# usb_uart.net
KiCad netlist of a schematic drawn in EAGLE
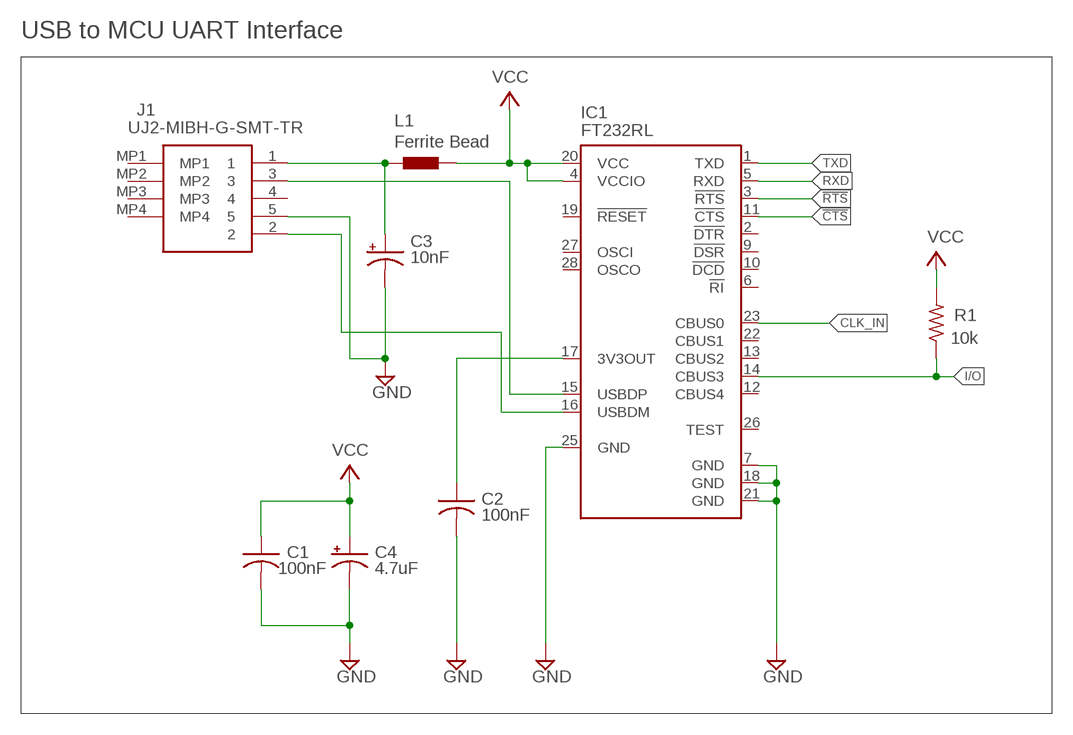
[diagram p0: schematic, sheet 1]

(export (version "E")
  (design (tool "Eeschema 10.0.6"))
  (components
    (comp (ref "C1")
      (value "100nF")
      (footprint "eagle-import:C0402")
      (libsource (lib "eagle-import") (part "C-USC0402"))
    )
    (comp (ref "C2")
      (value "100nF")
      (footprint "eagle-import:C0402")
      (libsource (lib "eagle-import") (part "C-USC0402"))
    )
    (comp (ref "C3")
      (value "10nF")
      (footprint "eagle-import:PANASONIC_A")
      (libsource (lib "eagle-import") (part "CPOL-USA"))
    )
    (comp (ref "C4")
      (value "4.7uF")
      (footprint "eagle-import:PANASONIC_D")
      (libsource (lib "eagle-import") (part "CPOL-USD"))
    )
    (comp (ref "IC1")
      (value "FT232RL")
      (footprint "eagle-import:SSOP28")
      (libsource (lib "eagle-import") (part "FT232RL"))
    )
    (comp (ref "J1")
      (value "UJ2-MIBH-G-SMT-TR")
      (footprint "eagle-import:UJ2MIBHGSMTTR")
      (fields (field (name "MOUSER_PART_NUMBER") "490-UJ2-MIBH-G-SMTTR"))
      (libsource (lib "eagle-import") (part "UJ2-MIBH-G-SMT-TR"))
    )
    (comp (ref "L1")
      (value "Ferrite Bead")
      (footprint "eagle-import:0402")
      (libsource (lib "eagle-import") (part "BLM15HB121SN1"))
    )
    (comp (ref "R1")
      (value "10k")
      (footprint "eagle-import:R0402")
      (libsource (lib "eagle-import") (part "R-US_R0402"))
    )
  )
  (nets
    (net (code "1") (name "/~{CTS}") (class "Default")
      (node (ref "IC1") (pin "11") (pinfunction "~{CTS}_11") (pintype "input"))
    )
    (net (code "2") (name "/~{RTS}") (class "Default")
      (node (ref "IC1") (pin "3") (pinfunction "~{RTS}_3") (pintype "output"))
    )
    (net (code "3") (name "CLK_IN") (class "Default")
      (node (ref "IC1") (pin "23") (pinfunction "CBUS0_23") (pintype "bidirectional"))
    )
    (net (code "4") (name "GND") (class "Default")
      (node (ref "C1") (pin "2") (pinfunction "2_2") (pintype "passive"))
      (node (ref "C2") (pin "2") (pinfunction "2_2") (pintype "passive"))
      (node (ref "C3") (pin "-") (pinfunction "-_-") (pintype "passive"))
      (node (ref "C4") (pin "-") (pinfunction "-_-") (pintype "passive"))
      (node (ref "IC1") (pin "18") (pinfunction "GND_18") (pintype "power_in"))
      (node (ref "IC1") (pin "21") (pinfunction "GND_21") (pintype "power_in"))
      (node (ref "IC1") (pin "25") (pinfunction "GND_25") (pintype "power_in"))
      (node (ref "IC1") (pin "7") (pinfunction "GND_7") (pintype "power_in"))
      (node (ref "J1") (pin "5") (pinfunction "5_5") (pintype "bidirectional"))
    )
    (net (code "5") (name "I{slash}O") (class "Default")
      (node (ref "IC1") (pin "14") (pinfunction "CBUS3_14") (pintype "bidirectional"))
      (node (ref "R1") (pin "1") (pinfunction "1_1") (pintype "passive"))
    )
    (net (code "6") (name "Net-(C3-Pad+)") (class "Default")
      (node (ref "C3") (pin "+") (pinfunction "+_+") (pintype "passive"))
      (node (ref "J1") (pin "1") (pinfunction "1_1") (pintype "bidirectional"))
      (node (ref "L1") (pin "1") (pinfunction "1_1") (pintype "passive"))
    )
    (net (code "7") (name "Net-(IC1-3V3OUT)") (class "Default")
      (node (ref "C2") (pin "1") (pinfunction "1_1") (pintype "passive"))
      (node (ref "IC1") (pin "17") (pinfunction "3V3OUT_17") (pintype "output"))
    )
    (net (code "8") (name "Net-(IC1-USBDM)") (class "Default")
      (node (ref "IC1") (pin "16") (pinfunction "USBDM_16") (pintype "bidirectional"))
      (node (ref "J1") (pin "2") (pinfunction "2_2") (pintype "bidirectional"))
    )
    (net (code "9") (name "Net-(IC1-USBDP)") (class "Default")
      (node (ref "IC1") (pin "15") (pinfunction "USBDP_15") (pintype "bidirectional"))
      (node (ref "J1") (pin "3") (pinfunction "3_3") (pintype "bidirectional"))
    )
    (net (code "10") (name "RXD") (class "Default")
      (node (ref "IC1") (pin "5") (pinfunction "RXD_5") (pintype "input"))
    )
    (net (code "11") (name "TXD") (class "Default")
      (node (ref "IC1") (pin "1") (pinfunction "TXD_1") (pintype "output"))
    )
    (net (code "12") (name "VCC") (class "Default")
      (node (ref "C1") (pin "1") (pinfunction "1_1") (pintype "passive"))
      (node (ref "C4") (pin "+") (pinfunction "+_+") (pintype "passive"))
      (node (ref "IC1") (pin "20") (pinfunction "VCC_20") (pintype "power_in"))
      (node (ref "IC1") (pin "4") (pinfunction "VCCIO_4") (pintype "power_in"))
      (node (ref "L1") (pin "2") (pinfunction "2_2") (pintype "passive"))
      (node (ref "R1") (pin "2") (pinfunction "2_2") (pintype "passive"))
    )
    (net (code "13") (name "unconnected-(IC1-CBUS1-Pad22)") (class "Default")
      (node (ref "IC1") (pin "22") (pinfunction "CBUS1_22") (pintype "bidirectional"))
    )
    (net (code "14") (name "unconnected-(IC1-CBUS2-Pad13)") (class "Default")
      (node (ref "IC1") (pin "13") (pinfunction "CBUS2_13") (pintype "bidirectional"))
    )
    (net (code "15") (name "unconnected-(IC1-CBUS4-Pad12)") (class "Default")
      (node (ref "IC1") (pin "12") (pinfunction "CBUS4_12") (pintype "bidirectional"))
    )
    (net (code "16") (name "unconnected-(IC1-OSCI-Pad27)") (class "Default")
      (node (ref "IC1") (pin "27") (pinfunction "OSCI_27") (pintype "input"))
    )
    (net (code "17") (name "unconnected-(IC1-OSCO-Pad28)") (class "Default")
      (node (ref "IC1") (pin "28") (pinfunction "OSCO_28") (pintype "output"))
    )
    (net (code "18") (name "unconnected-(IC1-TEST-Pad26)") (class "Default")
      (node (ref "IC1") (pin "26") (pinfunction "TEST_26") (pintype "input"))
    )
    (net (code "19") (name "unconnected-(IC1-~{DCD}-Pad10)") (class "Default")
      (node (ref "IC1") (pin "10") (pinfunction "~{DCD}_10") (pintype "input"))
    )
    (net (code "20") (name "unconnected-(IC1-~{DSR}-Pad9)") (class "Default")
      (node (ref "IC1") (pin "9") (pinfunction "~{DSR}_9") (pintype "input"))
    )
    (net (code "21") (name "unconnected-(IC1-~{DTR}-Pad2)") (class "Default")
      (node (ref "IC1") (pin "2") (pinfunction "~{DTR}_2") (pintype "output"))
    )
    (net (code "22") (name "unconnected-(IC1-~{RESET}-Pad19)") (class "Default")
      (node (ref "IC1") (pin "19") (pinfunction "~{RESET}_19") (pintype "input"))
    )
    (net (code "23") (name "unconnected-(IC1-~{RI}-Pad6)") (class "Default")
      (node (ref "IC1") (pin "6") (pinfunction "~{RI}_6") (pintype "input"))
    )
    (net (code "24") (name "unconnected-(J1-Pad4)") (class "Default")
      (node (ref "J1") (pin "4") (pinfunction "4_4") (pintype "bidirectional"))
    )
    (net (code "25") (name "unconnected-(J1-PadMP1)") (class "Default")
      (node (ref "J1") (pin "MP1") (pinfunction "MP1_MP1") (pintype "bidirectional"))
    )
    (net (code "26") (name "unconnected-(J1-PadMP2)") (class "Default")
      (node (ref "J1") (pin "MP2") (pinfunction "MP2_MP2") (pintype "bidirectional"))
    )
    (net (code "27") (name "unconnected-(J1-PadMP3)") (class "Default")
      (node (ref "J1") (pin "MP3") (pinfunction "MP3_MP3") (pintype "bidirectional"))
    )
    (net (code "28") (name "unconnected-(J1-PadMP4)") (class "Default")
      (node (ref "J1") (pin "MP4") (pinfunction "MP4_MP4") (pintype "bidirectional"))
    )
  )
)
